# USB_PER1.net
KiCad netlist of a schematic drawn in Altium Designer
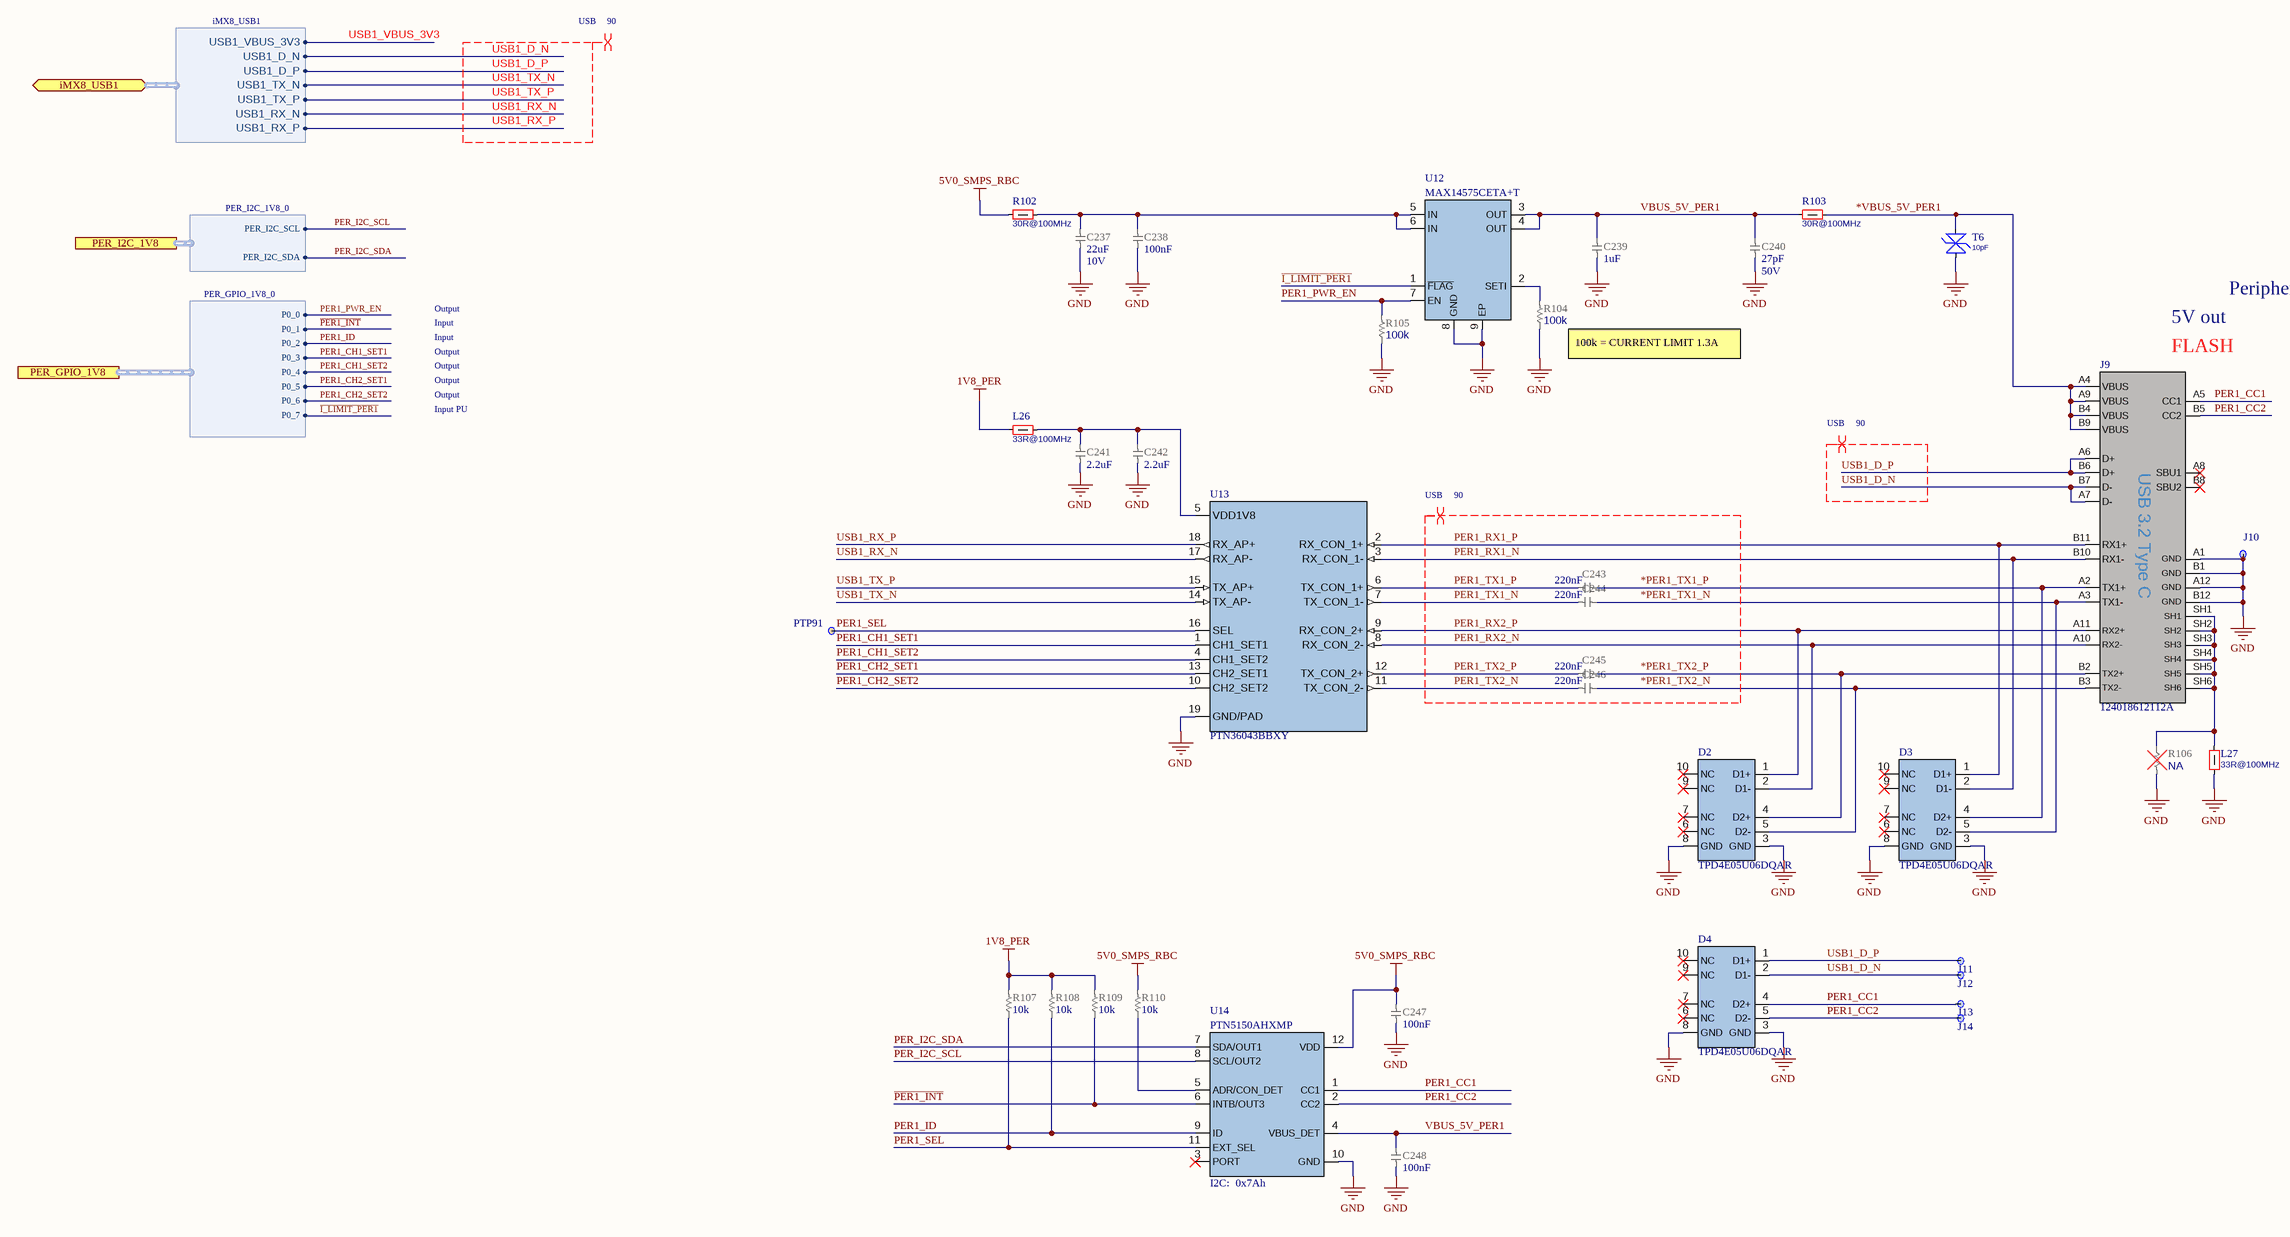
[diagram p0: USB_PER1.SchDoc]

(export (version "E")
  (design (tool "Eeschema 10.0.6"))
  (components
    (comp (ref "C237")
      (value "22uF")
      (footprint "CAP_0805_UN1Q")
      (description "CAP")
      (fields
        (field (name "VOLTAGE") "10V")
        (field (name "TOLERANCE") "+/-20%")
        (field (name "PART NUMBER") "GRM21BZ71A226ME15L")
      )
      (libsource (lib "robo_cam") (part "CMP-001-000892-11"))
    )
    (comp (ref "C238")
      (value "100nF")
      (footprint "CAP_0201_UN1Q")
      (description "CAP")
      (fields (field (name "PART NUMBER") "GRM033C71C104KE14D") (field (name "MANUFACTURER") "Murata"))
      (libsource (lib "robo_cam") (part "CMP-001-000385-16"))
    )
    (comp (ref "C239")
      (value "1uF")
      (footprint "CAP_0201_UN1Q")
      (description "CAP")
      (fields (field (name "PART NUMBER") "KGM03CS61A105MH") (field (name "MANUFACTURER") "Kyocera"))
      (libsource (lib "robo_cam") (part "CMP-001-000336-15"))
    )
    (comp (ref "C240")
      (value "27pF")
      (footprint "CAP_0201_UN1Q")
      (description "CAP")
      (fields
        (field (name "PART NUMBER") "GRM0335C1H270JA01D")
        (field (name "MANUFACTURER") "TDK")
        (field (name "VOLTAGE") "50V")
      )
      (libsource (lib "robo_cam") (part "CMP-001-000280-15"))
    )
    (comp (ref "C241")
      (value "2.2uF")
      (footprint "CAP_0402_H09W07_UN1Q")
      (description "CAP")
      (fields (field (name "PART NUMBER") "GRM155C81A225KE44D") (field (name "MANUFACTURER") "Murata"))
      (libsource (lib "robo_cam") (part "CMP-001-000887-10"))
    )
    (comp (ref "C242")
      (value "2.2uF")
      (footprint "CAP_0402_H09W07_UN1Q")
      (description "CAP")
      (fields (field (name "PART NUMBER") "GRM155C81A225KE44D") (field (name "MANUFACTURER") "Murata"))
      (libsource (lib "robo_cam") (part "CMP-001-000887-10"))
    )
    (comp (ref "C243")
      (value "220nF")
      (footprint "CAP_0201_UN1Q")
      (description "CAP")
      (fields (field (name "PART NUMBER") "GRM033C81A224KE01D") (field (name "MANUFACTURER") "Murata"))
      (libsource (lib "robo_cam") (part "CMP-001-000889-11"))
    )
    (comp (ref "C244")
      (value "220nF")
      (footprint "CAP_0201_UN1Q")
      (description "CAP")
      (fields (field (name "PART NUMBER") "GRM033C81A224KE01D") (field (name "MANUFACTURER") "Murata"))
      (libsource (lib "robo_cam") (part "CMP-001-000889-11"))
    )
    (comp (ref "C245")
      (value "220nF")
      (footprint "CAP_0201_UN1Q")
      (description "CAP")
      (fields (field (name "PART NUMBER") "GRM033C81A224KE01D") (field (name "MANUFACTURER") "Murata"))
      (libsource (lib "robo_cam") (part "CMP-001-000889-11"))
    )
    (comp (ref "C246")
      (value "220nF")
      (footprint "CAP_0201_UN1Q")
      (description "CAP")
      (fields (field (name "PART NUMBER") "GRM033C81A224KE01D") (field (name "MANUFACTURER") "Murata"))
      (libsource (lib "robo_cam") (part "CMP-001-000889-11"))
    )
    (comp (ref "C247")
      (value "100nF")
      (footprint "CAP_0201_UN1Q")
      (description "CAP")
      (fields (field (name "PART NUMBER") "GRM033C71C104KE14D") (field (name "MANUFACTURER") "Murata"))
      (libsource (lib "robo_cam") (part "CMP-001-000385-16"))
    )
    (comp (ref "C248")
      (value "100nF")
      (footprint "CAP_0201_UN1Q")
      (description "CAP")
      (fields (field (name "PART NUMBER") "GRM033C71C104KE14D") (field (name "MANUFACTURER") "Murata"))
      (libsource (lib "robo_cam") (part "CMP-001-000385-16"))
    )
    (comp (ref "D2")
      (value "TPD4E05U06DQAR")
      (footprint "USON10_DQA_TI")
      (description "4-CH Low-Capacitance ESD Diode")
      (fields
        (field (name "MANUFACTURER") "Texas Instruments")
        (field (name "SOURCE") "UUDET_KOMPONENTIT.SchLib")
      )
      (libsource (lib "robo_cam") (part "CMP-001-000916-4"))
    )
    (comp (ref "D3")
      (value "TPD4E05U06DQAR")
      (footprint "USON10_DQA_TI")
      (description "4-CH Low-Capacitance ESD Diode")
      (fields
        (field (name "MANUFACTURER") "Texas Instruments")
        (field (name "SOURCE") "UUDET_KOMPONENTIT.SchLib")
      )
      (libsource (lib "robo_cam") (part "CMP-001-000916-4"))
    )
    (comp (ref "D4")
      (value "TPD4E05U06DQAR")
      (footprint "USON10_DQA_TI")
      (description "4-CH Low-Capacitance ESD Diode")
      (fields
        (field (name "MANUFACTURER") "Texas Instruments")
        (field (name "SOURCE") "UUDET_KOMPONENTIT.SchLib")
      )
      (libsource (lib "robo_cam") (part "CMP-001-000916-4"))
    )
    (comp (ref "J9")
      (value "USB_C_AMPHENOL_124018612112A")
      (footprint "USB_C_AMPHENOL_124018612112A")
      (description "USB3.2 GEN1, Type C, Top mount, CH 1.50mm, Dual Row SMT, IPX8")
      (fields
        (field (name "PART NUMBER") "124018612112A")
        (field (name "MANUFACTURER") "Amphenol")
        (field (name "MANUFACTURER PART NUMBER") "12402082E512A")
      )
      (libsource (lib "robo_cam") (part "CMP-001-001438-8"))
    )
    (comp (ref "J10")
      (value "Testpoint, Surface, 1.0mm")
      (footprint "TP_1mm_UN1Q")
      (description "Testpoint 1.0mm")
      (fields (field (name "PART NUMBER") "TP 1mm"))
      (libsource (lib "TII_WS") (part "TP_1mm"))
    )
    (comp (ref "J11")
      (value "Testpoint, Surface, 1.0mm")
      (footprint "TP_1mm_UN1Q")
      (description "Testpoint 1.0mm")
      (fields (field (name "PART NUMBER") "TP 1mm"))
      (libsource (lib "robo_cam") (part "CMP-001-000153-12"))
    )
    (comp (ref "J12")
      (value "Testpoint, Surface, 1.0mm")
      (footprint "TP_1mm_UN1Q")
      (description "Testpoint 1.0mm")
      (fields (field (name "PART NUMBER") "TP 1mm"))
      (libsource (lib "robo_cam") (part "CMP-001-000153-12"))
    )
    (comp (ref "J13")
      (value "Testpoint, Surface, 1.0mm")
      (footprint "TP_1mm_UN1Q")
      (description "Testpoint 1.0mm")
      (fields (field (name "PART NUMBER") "TP 1mm"))
      (libsource (lib "robo_cam") (part "CMP-001-000153-12"))
    )
    (comp (ref "J14")
      (value "Testpoint, Surface, 1.0mm")
      (footprint "TP_1mm_UN1Q")
      (description "Testpoint 1.0mm")
      (fields (field (name "PART NUMBER") "TP 1mm"))
      (libsource (lib "robo_cam") (part "CMP-001-000153-12"))
    )
    (comp (ref "L26")
      (value "33R@100MHz")
      (footprint "IND_0201_UN1Q")
      (description "FERRITE")
      (fields (field (name "MANUFACTURER") "Murata") (field (name "TOLERANCE") "25%"))
      (libsource (lib "robo_cam") (part "CMP-001-000744-7"))
    )
    (comp (ref "L27")
      (value "33R@100MHz")
      (footprint "IND_0201_UN1Q")
      (description "FERRITE")
      (fields (field (name "MANUFACTURER") "Murata") (field (name "TOLERANCE") "25%"))
      (libsource (lib "robo_cam") (part "CMP-001-000744-7"))
    )
    (comp (ref "PTP91")
      (value "PTP_0.4mm")
      (footprint "PTP_0.4mm")
      (description "Production Testpoint 0.4mm. Flying probe. Use 1mm pitch.")
      (fields (field (name "PART NUMBER") "PTP 0.4mm"))
      (libsource (lib "robo_cam") (part "CMP-001-001296-3"))
    )
    (comp (ref "R102")
      (value "30R@100MHz")
      (footprint "FERR_BLM15KD")
      (description "FERRITE")
      (fields (field (name "PART NUMBER") "BLM15KD300SN1") (field (name "MANUFACTURER") "Murata"))
      (libsource (lib "robo_cam") (part "CMP-001-000738-12"))
    )
    (comp (ref "R103")
      (value "30R@100MHz")
      (footprint "FERR_BLM15KD")
      (description "FERRITE")
      (fields (field (name "PART NUMBER") "BLM15KD300SN1") (field (name "MANUFACTURER") "Murata"))
      (libsource (lib "robo_cam") (part "CMP-001-000738-12"))
    )
    (comp (ref "R104")
      (value "100k")
      (footprint "RES_0201_UN1Q")
      (description "RES")
      (fields (field (name "TOLERANCE") "1%") (field (name "PART NUMBER") "RC0201FR-07100KL"))
      (libsource (lib "robo_cam") (part "CMP-001-000526-11"))
    )
    (comp (ref "R105")
      (value "100k")
      (footprint "RES_0201_UN1Q")
      (description "RES")
      (fields (field (name "TOLERANCE") "1%") (field (name "PART NUMBER") "RC0201FR-07100KL"))
      (libsource (lib "robo_cam") (part "CMP-001-000526-11"))
    )
    (comp (ref "R106")
      (value "NA")
      (footprint "RES_0201_UN1Q")
      (description "Not Assembled - RES")
      (fields (field (name "Comment") "RES_0201_NA"))
      (libsource (lib "robo_cam") (part "CMP-001-000434-10"))
    )
    (comp (ref "R107")
      (value "10k")
      (footprint "RES_0201_UN1Q")
      (description "RES")
      (fields (field (name "PART NUMBER") "RC0201FR-0710KL") (field (name "MANUFACTURER") "YAGEO"))
      (libsource (lib "robo_cam") (part "CMP-001-000446-13"))
    )
    (comp (ref "R108")
      (value "10k")
      (footprint "RES_0201_UN1Q")
      (description "RES")
      (fields (field (name "PART NUMBER") "RC0201FR-0710KL") (field (name "MANUFACTURER") "YAGEO"))
      (libsource (lib "robo_cam") (part "CMP-001-000446-13"))
    )
    (comp (ref "R109")
      (value "10k")
      (footprint "RES_0201_UN1Q")
      (description "RES")
      (fields (field (name "PART NUMBER") "RC0201FR-0710KL") (field (name "MANUFACTURER") "YAGEO"))
      (libsource (lib "robo_cam") (part "CMP-001-000446-13"))
    )
    (comp (ref "R110")
      (value "10k")
      (footprint "RES_0201_UN1Q")
      (description "RES")
      (fields (field (name "PART NUMBER") "RC0201FR-0710KL") (field (name "MANUFACTURER") "YAGEO"))
      (libsource (lib "robo_cam") (part "CMP-001-000446-13"))
    )
    (comp (ref "T6")
      (value "10pF")
      (footprint "TVS_0201_EZAEG")
      (description "ESD Protection  TVS Diodes SMP Diode 0201 5vdc 10 pf <8v clamp@1a")
      (fields (field (name "PART NUMBER") "GG020105100N2P") (field (name "MANUFACTURER") "TDK"))
      (libsource (lib "robo_cam") (part "CMP-001-000756-6"))
    )
    (comp (ref "U12")
      (value "MAX14575C")
      (footprint "TDFN8-MAX14575C")
      (description "ADJ. CURRENT-LIMITED POWER SWITCH, 2.5A")
      (fields (field (name "PART NUMBER") "MAX14575CETA+T") (field (name "MANUFACTURER") "Maxim Integrated"))
      (libsource (lib "TII_WS") (part "MAX14575C"))
    )
    (comp (ref "U13")
      (value "PTN36043BBXY")
      (footprint "DHX2QFN18_NXP")
      (description "USB3.1 Gen1 Type-C Superspeed Active Signal Switch")
      (fields
        (field (name "MANUFACTURER") "NXP")
        (field (name "PART NUMBER") "PTN36043BBXY")
        (field (name "MANUFACTURER_1") "Knowles")
      )
      (libsource (lib "robo_cam") (part "CMP-001-001164-4"))
    )
    (comp (ref "U14")
      (value "PTN5150AHXMP")
      (footprint "X2QFN12_NXP")
      (description "CC logic for USB Type-C applications")
      (fields (field (name "MANUFACTURER") "NXP") (field (name "PART NUMBER") "PTN5150AHXMP"))
      (libsource (lib "TII_WS") (part "PTN5150AHXMP"))
    )
  )
  (nets
    (net (code "4") (name "/*PER1_TX1_N") (class "Default")
      (node (ref "C244") (pin "1") (pinfunction "1_1") (pintype "passive"))
      (node (ref "D3") (pin "5") (pinfunction "D2-_5") (pintype "passive"))
      (node (ref "J9") (pin "A3") (pinfunction "TX1-_A3") (pintype "passive"))
    )
    (net (code "5") (name "/*PER1_TX1_P") (class "Default")
      (node (ref "C243") (pin "1") (pinfunction "1_1") (pintype "passive"))
      (node (ref "D3") (pin "4") (pinfunction "D2+_4") (pintype "passive"))
      (node (ref "J9") (pin "A2") (pinfunction "TX1+_A2") (pintype "passive"))
    )
    (net (code "6") (name "/*PER1_TX2_N") (class "Default")
      (node (ref "C246") (pin "1") (pinfunction "1_1") (pintype "passive"))
      (node (ref "D2") (pin "5") (pinfunction "D2-_5") (pintype "passive"))
      (node (ref "J9") (pin "B3") (pinfunction "TX2-_B3") (pintype "passive"))
    )
    (net (code "7") (name "/*PER1_TX2_P") (class "Default")
      (node (ref "C245") (pin "1") (pinfunction "1_1") (pintype "passive"))
      (node (ref "D2") (pin "4") (pinfunction "D2+_4") (pintype "passive"))
      (node (ref "J9") (pin "B2") (pinfunction "TX2+_B2") (pintype "passive"))
    )
    (net (code "8") (name "/*VBUS_5V_PER1") (class "Default")
      (node (ref "J9") (pin "A4") (pinfunction "VBUS_A4") (pintype "passive"))
      (node (ref "J9") (pin "A9") (pinfunction "VBUS_A9") (pintype "passive"))
      (node (ref "J9") (pin "B4") (pinfunction "VBUS_B4") (pintype "passive"))
      (node (ref "J9") (pin "B9") (pinfunction "VBUS_B9") (pintype "passive"))
      (node (ref "R103") (pin "2") (pinfunction "2_2") (pintype "passive"))
      (node (ref "T6") (pin "2") (pinfunction "2_2") (pintype "passive"))
    )
    (net (code "9") (name "/I_LIMIT_PER1") (class "Default")
      (node (ref "U12") (pin "1") (pinfunction "~{FLAG}_1") (pintype "passive"))
    )
    (net (code "10") (name "/PER1_CC1") (class "Default")
      (node (ref "D4") (pin "4") (pinfunction "D2+_4") (pintype "passive"))
      (node (ref "J13") (pin "1") (pinfunction "TP_1") (pintype "passive"))
      (node (ref "J9") (pin "A5") (pinfunction "CC1_A5") (pintype "passive"))
      (node (ref "U14") (pin "1") (pinfunction "CC1_1") (pintype "passive"))
    )
    (net (code "11") (name "/PER1_CC2") (class "Default")
      (node (ref "D4") (pin "5") (pinfunction "D2-_5") (pintype "passive"))
      (node (ref "J14") (pin "1") (pinfunction "TP_1") (pintype "passive"))
      (node (ref "J9") (pin "B5") (pinfunction "CC2_B5") (pintype "passive"))
      (node (ref "U14") (pin "2") (pinfunction "CC2_2") (pintype "passive"))
    )
    (net (code "12") (name "/PER1_CH1_SET1") (class "Default")
      (node (ref "U13") (pin "1") (pinfunction "CH1_SET1_1") (pintype "passive"))
    )
    (net (code "13") (name "/PER1_CH1_SET2") (class "Default")
      (node (ref "U13") (pin "4") (pinfunction "CH1_SET2_4") (pintype "passive"))
    )
    (net (code "14") (name "/PER1_CH2_SET1") (class "Default")
      (node (ref "U13") (pin "13") (pinfunction "CH2_SET1_13") (pintype "passive"))
    )
    (net (code "15") (name "/PER1_CH2_SET2") (class "Default")
      (node (ref "U13") (pin "10") (pinfunction "CH2_SET2_10") (pintype "passive"))
    )
    (net (code "16") (name "/PER1_ID") (class "Default")
      (node (ref "R108") (pin "1") (pinfunction "1_1") (pintype "passive"))
      (node (ref "U14") (pin "9") (pinfunction "ID_9") (pintype "passive"))
    )
    (net (code "17") (name "/PER1_INT") (class "Default")
      (node (ref "R109") (pin "1") (pinfunction "1_1") (pintype "passive"))
      (node (ref "U14") (pin "6") (pinfunction "INTB/OUT3_6") (pintype "passive"))
    )
    (net (code "18") (name "/PER1_PWR_EN") (class "Default")
      (node (ref "R105") (pin "2") (pinfunction "2_2") (pintype "passive"))
      (node (ref "U12") (pin "7") (pinfunction "EN_7") (pintype "passive"))
    )
    (net (code "19") (name "/PER1_RX1_N") (class "Default")
      (node (ref "D3") (pin "2") (pinfunction "D1-_2") (pintype "passive"))
      (node (ref "J9") (pin "B10") (pinfunction "RX1-_B10") (pintype "passive"))
      (node (ref "U13") (pin "3") (pinfunction "RX_CON_1-_3") (pintype "input"))
    )
    (net (code "20") (name "/PER1_RX1_P") (class "Default")
      (node (ref "D3") (pin "1") (pinfunction "D1+_1") (pintype "passive"))
      (node (ref "J9") (pin "B11") (pinfunction "RX1+_B11") (pintype "passive"))
      (node (ref "U13") (pin "2") (pinfunction "RX_CON_1+_2") (pintype "input"))
    )
    (net (code "21") (name "/PER1_RX2_N") (class "Default")
      (node (ref "D2") (pin "2") (pinfunction "D1-_2") (pintype "passive"))
      (node (ref "J9") (pin "A10") (pinfunction "RX2-_A10") (pintype "passive"))
      (node (ref "U13") (pin "8") (pinfunction "RX_CON_2-_8") (pintype "input"))
    )
    (net (code "22") (name "/PER1_RX2_P") (class "Default")
      (node (ref "D2") (pin "1") (pinfunction "D1+_1") (pintype "passive"))
      (node (ref "J9") (pin "A11") (pinfunction "RX2+_A11") (pintype "passive"))
      (node (ref "U13") (pin "9") (pinfunction "RX_CON_2+_9") (pintype "input"))
    )
    (net (code "23") (name "/PER1_SEL") (class "Default")
      (node (ref "PTP91") (pin "1") (pinfunction "TP_1") (pintype "passive"))
      (node (ref "R107") (pin "1") (pinfunction "1_1") (pintype "passive"))
      (node (ref "U13") (pin "16") (pinfunction "SEL_16") (pintype "passive"))
      (node (ref "U14") (pin "11") (pinfunction "EXT_SEL_11") (pintype "passive"))
    )
    (net (code "24") (name "/PER1_TX1_N") (class "Default")
      (node (ref "C244") (pin "2") (pinfunction "2_2") (pintype "passive"))
      (node (ref "U13") (pin "7") (pinfunction "TX_CON_1-_7") (pintype "output"))
    )
    (net (code "25") (name "/PER1_TX1_P") (class "Default")
      (node (ref "C243") (pin "2") (pinfunction "2_2") (pintype "passive"))
      (node (ref "U13") (pin "6") (pinfunction "TX_CON_1+_6") (pintype "output"))
    )
    (net (code "26") (name "/PER1_TX2_N") (class "Default")
      (node (ref "C246") (pin "2") (pinfunction "2_2") (pintype "passive"))
      (node (ref "U13") (pin "11") (pinfunction "TX_CON_2-_11") (pintype "output"))
    )
    (net (code "27") (name "/PER1_TX2_P") (class "Default")
      (node (ref "C245") (pin "2") (pinfunction "2_2") (pintype "passive"))
      (node (ref "U13") (pin "12") (pinfunction "TX_CON_2+_12") (pintype "output"))
    )
    (net (code "28") (name "/PER_I2C_SCL") (class "Default")
      (node (ref "U14") (pin "8") (pinfunction "SCL/OUT2_8") (pintype "passive"))
    )
    (net (code "29") (name "/PER_I2C_SDA") (class "Default")
      (node (ref "U14") (pin "7") (pinfunction "SDA/OUT1_7") (pintype "passive"))
    )
    (net (code "30") (name "/USB1_D_N") (class "Default")
      (node (ref "D4") (pin "2") (pinfunction "D1-_2") (pintype "passive"))
      (node (ref "J12") (pin "1") (pinfunction "TP_1") (pintype "passive"))
      (node (ref "J9") (pin "A7") (pinfunction "D-_A7") (pintype "passive"))
      (node (ref "J9") (pin "B7") (pinfunction "D-_B7") (pintype "passive"))
    )
    (net (code "31") (name "/USB1_D_P") (class "Default")
      (node (ref "D4") (pin "1") (pinfunction "D1+_1") (pintype "passive"))
      (node (ref "J11") (pin "1") (pinfunction "TP_1") (pintype "passive"))
      (node (ref "J9") (pin "A6") (pinfunction "D+_A6") (pintype "passive"))
      (node (ref "J9") (pin "B6") (pinfunction "D+_B6") (pintype "passive"))
    )
    (net (code "32") (name "/USB1_RX_N") (class "Default")
      (node (ref "U13") (pin "17") (pinfunction "RX_AP-_17") (pintype "output"))
    )
    (net (code "33") (name "/USB1_RX_P") (class "Default")
      (node (ref "U13") (pin "18") (pinfunction "RX_AP+_18") (pintype "output"))
    )
    (net (code "34") (name "/USB1_TX_N") (class "Default")
      (node (ref "U13") (pin "14") (pinfunction "TX_AP-_14") (pintype "input"))
    )
    (net (code "35") (name "/USB1_TX_P") (class "Default")
      (node (ref "U13") (pin "15") (pinfunction "TX_AP+_15") (pintype "input"))
    )
    (net (code "37") (name "/VBUS_5V_PER1") (class "Default")
      (node (ref "C239") (pin "2") (pinfunction "2_2") (pintype "passive"))
      (node (ref "C240") (pin "2") (pinfunction "2_2") (pintype "passive"))
      (node (ref "C248") (pin "1") (pinfunction "1_1") (pintype "passive"))
      (node (ref "R103") (pin "1") (pinfunction "1_1") (pintype "passive"))
      (node (ref "U12") (pin "3") (pinfunction "OUT_3") (pintype "passive"))
      (node (ref "U12") (pin "4") (pinfunction "OUT_4") (pintype "passive"))
      (node (ref "U14") (pin "4") (pinfunction "VBUS_DET_4") (pintype "passive"))
    )
    (net (code "41") (name "1V8_PER") (class "Default")
      (node (ref "L26") (pin "1") (pinfunction "1_1") (pintype "passive"))
      (node (ref "R107") (pin "2") (pinfunction "2_2") (pintype "passive"))
      (node (ref "R108") (pin "2") (pinfunction "2_2") (pintype "passive"))
      (node (ref "R109") (pin "2") (pinfunction "2_2") (pintype "passive"))
    )
    (net (code "42") (name "5V0_SMPS_RBC") (class "Default")
      (node (ref "C247") (pin "1") (pinfunction "1_1") (pintype "passive"))
      (node (ref "R102") (pin "1") (pinfunction "1_1") (pintype "passive"))
      (node (ref "R110") (pin "2") (pinfunction "2_2") (pintype "passive"))
      (node (ref "U14") (pin "12") (pinfunction "VDD_12") (pintype "passive"))
    )
    (net (code "43") (name "GND") (class "Default")
      (node (ref "C237") (pin "1") (pinfunction "1_1") (pintype "passive"))
      (node (ref "C238") (pin "1") (pinfunction "1_1") (pintype "passive"))
      (node (ref "C239") (pin "1") (pinfunction "1_1") (pintype "passive"))
      (node (ref "C240") (pin "1") (pinfunction "1_1") (pintype "passive"))
      (node (ref "C241") (pin "2") (pinfunction "2_2") (pintype "passive"))
      (node (ref "C242") (pin "2") (pinfunction "2_2") (pintype "passive"))
      (node (ref "C247") (pin "2") (pinfunction "2_2") (pintype "passive"))
      (node (ref "C248") (pin "2") (pinfunction "2_2") (pintype "passive"))
      (node (ref "D2") (pin "3") (pinfunction "GND_3") (pintype "passive"))
      (node (ref "D2") (pin "8") (pinfunction "GND_8") (pintype "passive"))
      (node (ref "D3") (pin "3") (pinfunction "GND_3") (pintype "passive"))
      (node (ref "D3") (pin "8") (pinfunction "GND_8") (pintype "passive"))
      (node (ref "D4") (pin "3") (pinfunction "GND_3") (pintype "passive"))
      (node (ref "D4") (pin "8") (pinfunction "GND_8") (pintype "passive"))
      (node (ref "J10") (pin "1") (pinfunction "TP_1") (pintype "passive"))
      (node (ref "J9") (pin "A1") (pinfunction "GND_A1") (pintype "passive"))
      (node (ref "J9") (pin "A12") (pinfunction "GND_A12") (pintype "passive"))
      (node (ref "J9") (pin "B1") (pinfunction "GND_B1") (pintype "passive"))
      (node (ref "J9") (pin "B12") (pinfunction "GND_B12") (pintype "passive"))
      (node (ref "L27") (pin "2") (pinfunction "2_2") (pintype "passive"))
      (node (ref "R104") (pin "1") (pinfunction "1_1") (pintype "passive"))
      (node (ref "R105") (pin "1") (pinfunction "1_1") (pintype "passive"))
      (node (ref "R106") (pin "2") (pinfunction "2_2") (pintype "passive"))
      (node (ref "T6") (pin "1") (pinfunction "1_1") (pintype "passive"))
      (node (ref "U12") (pin "8") (pinfunction "GND_8") (pintype "passive"))
      (node (ref "U12") (pin "9") (pinfunction "EP_9") (pintype "passive"))
      (node (ref "U13") (pin "19") (pinfunction "GND/PAD_19") (pintype "passive"))
      (node (ref "U14") (pin "10") (pinfunction "GND_10") (pintype "passive"))
    )
    (net (code "44") (name "Net-(C237-Pad2)") (class "Default")
      (node (ref "C237") (pin "2") (pinfunction "2_2") (pintype "passive"))
      (node (ref "C238") (pin "2") (pinfunction "2_2") (pintype "passive"))
      (node (ref "R102") (pin "2") (pinfunction "2_2") (pintype "passive"))
      (node (ref "U12") (pin "5") (pinfunction "IN_5") (pintype "passive"))
      (node (ref "U12") (pin "6") (pinfunction "IN_6") (pintype "passive"))
    )
    (net (code "45") (name "Net-(J9-PadSH1)") (class "Default")
      (node (ref "J9") (pin "SH1") (pinfunction "SH1_SH1") (pintype "passive"))
      (node (ref "J9") (pin "SH2") (pinfunction "SH2_SH2") (pintype "passive"))
      (node (ref "J9") (pin "SH3") (pinfunction "SH3_SH3") (pintype "passive"))
      (node (ref "J9") (pin "SH4") (pinfunction "SH4_SH4") (pintype "passive"))
      (node (ref "J9") (pin "SH5") (pinfunction "SH5_SH5") (pintype "passive"))
      (node (ref "J9") (pin "SH6") (pinfunction "SH6_SH6") (pintype "passive"))
      (node (ref "L27") (pin "1") (pinfunction "1_1") (pintype "passive"))
      (node (ref "R106") (pin "1") (pinfunction "1_1") (pintype "passive"))
    )
    (net (code "46") (name "Net-(U12-SETI)") (class "Default")
      (node (ref "R104") (pin "2") (pinfunction "2_2") (pintype "passive"))
      (node (ref "U12") (pin "2") (pinfunction "SETI_2") (pintype "passive"))
    )
    (net (code "47") (name "Net-(U13-VDD1V8)") (class "Default")
      (node (ref "C241") (pin "1") (pinfunction "1_1") (pintype "passive"))
      (node (ref "C242") (pin "1") (pinfunction "1_1") (pintype "passive"))
      (node (ref "L26") (pin "2") (pinfunction "2_2") (pintype "passive"))
      (node (ref "U13") (pin "5") (pinfunction "VDD1V8_5") (pintype "passive"))
    )
    (net (code "48") (name "Net-(U14-ADR{slash}CON_DET)") (class "Default")
      (node (ref "R110") (pin "1") (pinfunction "1_1") (pintype "passive"))
      (node (ref "U14") (pin "5") (pinfunction "ADR/CON_DET_5") (pintype "passive"))
    )
    (net (code "49") (name "unconnected-(D2-NC-Pad6)") (class "Default")
      (node (ref "D2") (pin "6") (pinfunction "NC_6") (pintype "passive+no_connect"))
    )
    (net (code "50") (name "unconnected-(D2-NC-Pad7)") (class "Default")
      (node (ref "D2") (pin "7") (pinfunction "NC_7") (pintype "passive+no_connect"))
    )
    (net (code "51") (name "unconnected-(D2-NC-Pad9)") (class "Default")
      (node (ref "D2") (pin "9") (pinfunction "NC_9") (pintype "passive+no_connect"))
    )
    (net (code "52") (name "unconnected-(D2-NC-Pad10)") (class "Default")
      (node (ref "D2") (pin "10") (pinfunction "NC_10") (pintype "passive+no_connect"))
    )
    (net (code "53") (name "unconnected-(D3-NC-Pad6)") (class "Default")
      (node (ref "D3") (pin "6") (pinfunction "NC_6") (pintype "passive+no_connect"))
    )
    (net (code "54") (name "unconnected-(D3-NC-Pad7)") (class "Default")
      (node (ref "D3") (pin "7") (pinfunction "NC_7") (pintype "passive+no_connect"))
    )
    (net (code "55") (name "unconnected-(D3-NC-Pad9)") (class "Default")
      (node (ref "D3") (pin "9") (pinfunction "NC_9") (pintype "passive+no_connect"))
    )
    (net (code "56") (name "unconnected-(D3-NC-Pad10)") (class "Default")
      (node (ref "D3") (pin "10") (pinfunction "NC_10") (pintype "passive+no_connect"))
    )
    (net (code "57") (name "unconnected-(D4-NC-Pad6)") (class "Default")
      (node (ref "D4") (pin "6") (pinfunction "NC_6") (pintype "passive+no_connect"))
    )
    (net (code "58") (name "unconnected-(D4-NC-Pad7)") (class "Default")
      (node (ref "D4") (pin "7") (pinfunction "NC_7") (pintype "passive+no_connect"))
    )
    (net (code "59") (name "unconnected-(D4-NC-Pad9)") (class "Default")
      (node (ref "D4") (pin "9") (pinfunction "NC_9") (pintype "passive+no_connect"))
    )
    (net (code "60") (name "unconnected-(D4-NC-Pad10)") (class "Default")
      (node (ref "D4") (pin "10") (pinfunction "NC_10") (pintype "passive+no_connect"))
    )
    (net (code "61") (name "unconnected-(J9-SBU1-PadA8)") (class "Default")
      (node (ref "J9") (pin "A8") (pinfunction "SBU1_A8") (pintype "passive+no_connect"))
    )
    (net (code "62") (name "unconnected-(J9-SBU2-PadB8)") (class "Default")
      (node (ref "J9") (pin "B8") (pinfunction "SBU2_B8") (pintype "passive+no_connect"))
    )
    (net (code "63") (name "unconnected-(U14-PORT-Pad3)") (class "Default")
      (node (ref "U14") (pin "3") (pinfunction "PORT_3") (pintype "passive+no_connect"))
    )
  )
)
